# shield.net
KiCad netlist of a schematic drawn in EAGLE
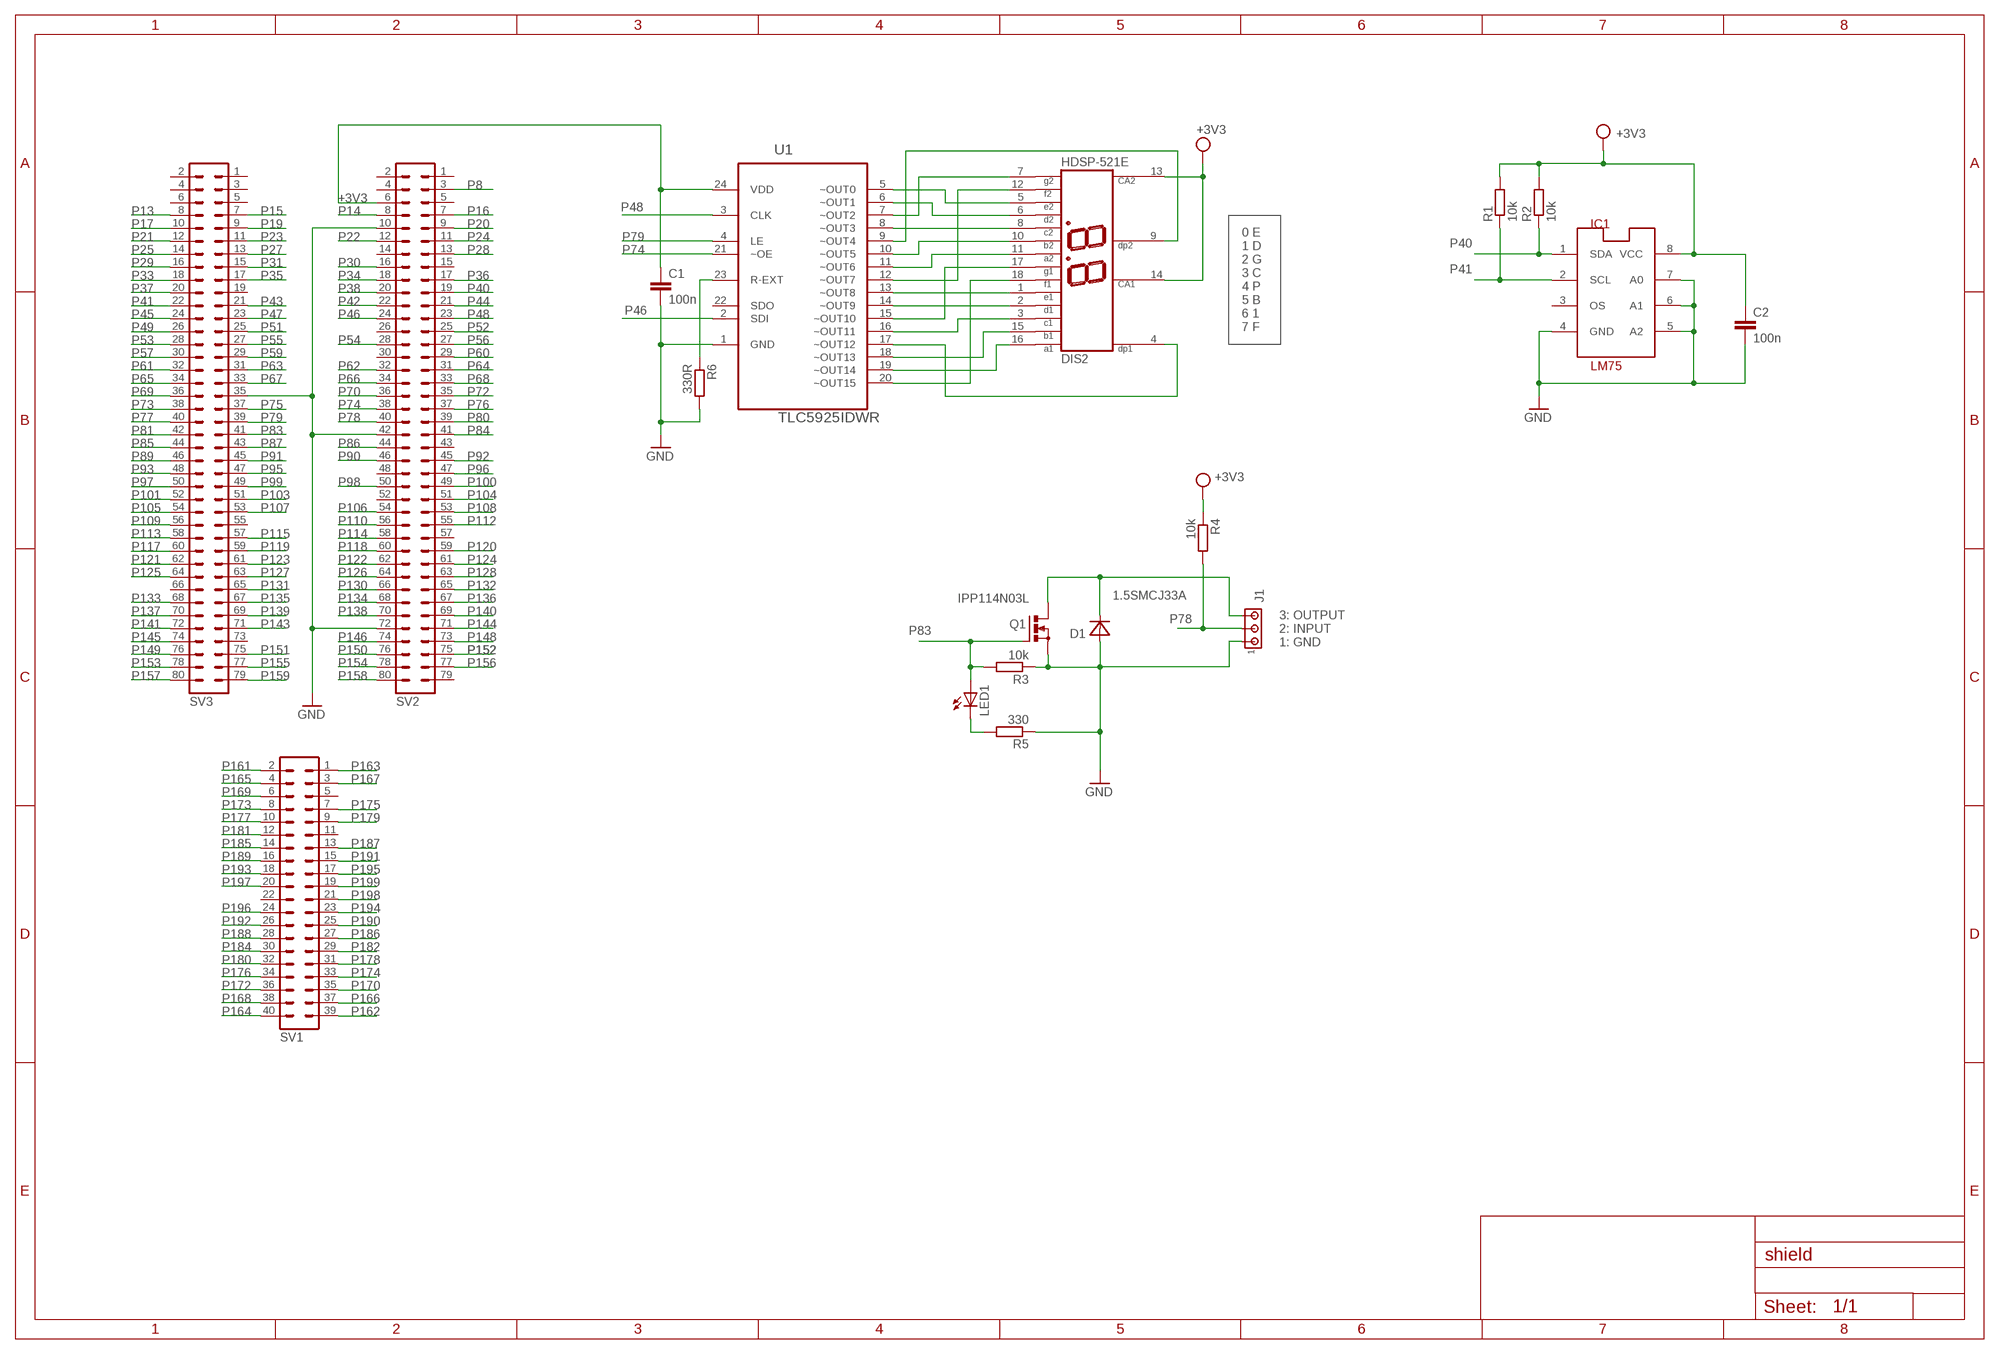
[diagram p0: schematic, sheet 1]

(export (version "E")
  (design (tool "Eeschema 10.0.6"))
  (components
    (comp (ref "C1")
      (value "100n")
      (footprint "eagle-import:C2.5-2")
      (libsource (lib "eagle-import") (part "C2.5/2"))
    )
    (comp (ref "C2")
      (value "100n")
      (footprint "eagle-import:C2.5-2")
      (libsource (lib "eagle-import") (part "C2.5/2"))
    )
    (comp (ref "D1")
      (value "1.5SMCJ33A")
      (footprint "eagle-import:DO214AB")
      (libsource (lib "eagle-import") (part "MBRS340"))
    )
    (comp (ref "DIS2")
      (value "HDSP-521E")
      (footprint "eagle-import:HDSP-R")
      (libsource (lib "eagle-import") (part "HD-K121"))
    )
    (comp (ref "IC1")
      (value "LM75")
      (footprint "eagle-import:SO8_LM75")
      (libsource (lib "eagle-import") (part "LM75_ICN"))
    )
    (comp (ref "J1")
      (value "MTA03-100")
      (footprint "eagle-import:10X03MTA")
      (libsource (lib "eagle-import") (part "MTA03-100"))
    )
    (comp (ref "LED1")
      (value "LED5MM")
      (footprint "eagle-import:LED5MM")
      (libsource (lib "eagle-import") (part "LED5MM"))
    )
    (comp (ref "Q1")
      (value "IPP114N03L")
      (footprint "eagle-import:TO220BV")
      (libsource (lib "eagle-import") (part "BUZ11BV"))
    )
    (comp (ref "R1")
      (value "10k")
      (footprint "eagle-import:0207_10")
      (libsource (lib "eagle-import") (part "R-EU_0207/10"))
    )
    (comp (ref "R2")
      (value "10k")
      (footprint "eagle-import:0207_10")
      (libsource (lib "eagle-import") (part "R-EU_0207/10"))
    )
    (comp (ref "R3")
      (value "10k")
      (footprint "eagle-import:0207_10")
      (libsource (lib "eagle-import") (part "R-EU_0207/10"))
    )
    (comp (ref "R4")
      (value "10k")
      (footprint "eagle-import:0207_10")
      (libsource (lib "eagle-import") (part "R-EU_0207/10"))
    )
    (comp (ref "R5")
      (value "330")
      (footprint "eagle-import:0207_10")
      (libsource (lib "eagle-import") (part "R-EU_0207/10"))
    )
    (comp (ref "R6")
      (value "330R")
      (footprint "eagle-import:0207_10")
      (libsource (lib "eagle-import") (part "R-EU_0207/10"))
    )
    (comp (ref "SV1")
      (value "MA20-2")
      (footprint "eagle-import:MA20-2")
      (libsource (lib "eagle-import") (part "MA20-2"))
    )
    (comp (ref "SV2")
      (value "MA40-2")
      (footprint "eagle-import:MA40-2")
      (libsource (lib "eagle-import") (part "MA40-2"))
    )
    (comp (ref "SV3")
      (value "MA40-2")
      (footprint "eagle-import:MA40-2")
      (libsource (lib "eagle-import") (part "MA40-2"))
    )
    (comp (ref "U1")
      (value "TLC5925IDWR")
      (footprint "eagle-import:SOIC127P1030X265-24N")
      (libsource (lib "eagle-import") (part "TLC5925IDWR"))
    )
  )
  (nets
    (net (code "1") (name "/P8") (class "Default")
      (node (ref "SV2") (pin "3") (pinfunction "3_3") (pintype "passive"))
    )
    (net (code "2") (name "/P13") (class "Default")
      (node (ref "SV3") (pin "8") (pinfunction "8_8") (pintype "passive"))
    )
    (net (code "3") (name "/P14") (class "Default")
      (node (ref "SV2") (pin "8") (pinfunction "8_8") (pintype "passive"))
    )
    (net (code "4") (name "/P15") (class "Default")
      (node (ref "SV3") (pin "7") (pinfunction "7_7") (pintype "passive"))
    )
    (net (code "5") (name "/P16") (class "Default")
      (node (ref "SV2") (pin "7") (pinfunction "7_7") (pintype "passive"))
    )
    (net (code "6") (name "/P17") (class "Default")
      (node (ref "SV3") (pin "10") (pinfunction "10_10") (pintype "passive"))
    )
    (net (code "7") (name "/P19") (class "Default")
      (node (ref "SV3") (pin "9") (pinfunction "9_9") (pintype "passive"))
    )
    (net (code "8") (name "/P20") (class "Default")
      (node (ref "SV2") (pin "9") (pinfunction "9_9") (pintype "passive"))
    )
    (net (code "9") (name "/P21") (class "Default")
      (node (ref "SV3") (pin "12") (pinfunction "12_12") (pintype "passive"))
    )
    (net (code "10") (name "/P22") (class "Default")
      (node (ref "SV2") (pin "12") (pinfunction "12_12") (pintype "passive"))
    )
    (net (code "11") (name "/P23") (class "Default")
      (node (ref "SV3") (pin "11") (pinfunction "11_11") (pintype "passive"))
    )
    (net (code "12") (name "/P24") (class "Default")
      (node (ref "SV2") (pin "11") (pinfunction "11_11") (pintype "passive"))
    )
    (net (code "13") (name "/P25") (class "Default")
      (node (ref "SV3") (pin "14") (pinfunction "14_14") (pintype "passive"))
    )
    (net (code "14") (name "/P27") (class "Default")
      (node (ref "SV3") (pin "13") (pinfunction "13_13") (pintype "passive"))
    )
    (net (code "15") (name "/P28") (class "Default")
      (node (ref "SV2") (pin "13") (pinfunction "13_13") (pintype "passive"))
    )
    (net (code "16") (name "/P29") (class "Default")
      (node (ref "SV3") (pin "16") (pinfunction "16_16") (pintype "passive"))
    )
    (net (code "17") (name "/P30") (class "Default")
      (node (ref "SV2") (pin "16") (pinfunction "16_16") (pintype "passive"))
    )
    (net (code "18") (name "/P31") (class "Default")
      (node (ref "SV3") (pin "15") (pinfunction "15_15") (pintype "passive"))
    )
    (net (code "19") (name "/P33") (class "Default")
      (node (ref "SV3") (pin "18") (pinfunction "18_18") (pintype "passive"))
    )
    (net (code "20") (name "/P34") (class "Default")
      (node (ref "SV2") (pin "18") (pinfunction "18_18") (pintype "passive"))
    )
    (net (code "21") (name "/P35") (class "Default")
      (node (ref "SV3") (pin "17") (pinfunction "17_17") (pintype "passive"))
    )
    (net (code "22") (name "/P36") (class "Default")
      (node (ref "SV2") (pin "17") (pinfunction "17_17") (pintype "passive"))
    )
    (net (code "23") (name "/P37") (class "Default")
      (node (ref "SV3") (pin "20") (pinfunction "20_20") (pintype "passive"))
    )
    (net (code "24") (name "/P38") (class "Default")
      (node (ref "SV2") (pin "20") (pinfunction "20_20") (pintype "passive"))
    )
    (net (code "25") (name "/P40") (class "Default")
      (node (ref "IC1") (pin "1") (pinfunction "SDA_1") (pintype "bidirectional"))
      (node (ref "R2") (pin "1") (pinfunction "1_1") (pintype "passive"))
      (node (ref "SV2") (pin "19") (pinfunction "19_19") (pintype "passive"))
    )
    (net (code "26") (name "/P41") (class "Default")
      (node (ref "IC1") (pin "2") (pinfunction "SCL_2") (pintype "bidirectional"))
      (node (ref "R1") (pin "1") (pinfunction "1_1") (pintype "passive"))
      (node (ref "SV3") (pin "22") (pinfunction "22_22") (pintype "passive"))
    )
    (net (code "27") (name "/P42") (class "Default")
      (node (ref "SV2") (pin "22") (pinfunction "22_22") (pintype "passive"))
    )
    (net (code "28") (name "/P43") (class "Default")
      (node (ref "SV3") (pin "21") (pinfunction "21_21") (pintype "passive"))
    )
    (net (code "29") (name "/P44") (class "Default")
      (node (ref "SV2") (pin "21") (pinfunction "21_21") (pintype "passive"))
    )
    (net (code "30") (name "/P45") (class "Default")
      (node (ref "SV3") (pin "24") (pinfunction "24_24") (pintype "passive"))
    )
    (net (code "31") (name "/P46") (class "Default")
      (node (ref "SV2") (pin "24") (pinfunction "24_24") (pintype "passive"))
      (node (ref "U1") (pin "2") (pinfunction "SDI_2") (pintype "input"))
    )
    (net (code "32") (name "/P47") (class "Default")
      (node (ref "SV3") (pin "23") (pinfunction "23_23") (pintype "passive"))
    )
    (net (code "33") (name "/P48") (class "Default")
      (node (ref "SV2") (pin "23") (pinfunction "23_23") (pintype "passive"))
      (node (ref "U1") (pin "3") (pinfunction "CLK_3") (pintype "input"))
    )
    (net (code "34") (name "/P49") (class "Default")
      (node (ref "SV3") (pin "26") (pinfunction "26_26") (pintype "passive"))
    )
    (net (code "35") (name "/P51") (class "Default")
      (node (ref "SV3") (pin "25") (pinfunction "25_25") (pintype "passive"))
    )
    (net (code "36") (name "/P52") (class "Default")
      (node (ref "SV2") (pin "25") (pinfunction "25_25") (pintype "passive"))
    )
    (net (code "37") (name "/P53") (class "Default")
      (node (ref "SV3") (pin "28") (pinfunction "28_28") (pintype "passive"))
    )
    (net (code "38") (name "/P54") (class "Default")
      (node (ref "SV2") (pin "28") (pinfunction "28_28") (pintype "passive"))
    )
    (net (code "39") (name "/P55") (class "Default")
      (node (ref "SV3") (pin "27") (pinfunction "27_27") (pintype "passive"))
    )
    (net (code "40") (name "/P56") (class "Default")
      (node (ref "SV2") (pin "27") (pinfunction "27_27") (pintype "passive"))
    )
    (net (code "41") (name "/P57") (class "Default")
      (node (ref "SV3") (pin "30") (pinfunction "30_30") (pintype "passive"))
    )
    (net (code "42") (name "/P59") (class "Default")
      (node (ref "SV3") (pin "29") (pinfunction "29_29") (pintype "passive"))
    )
    (net (code "43") (name "/P60") (class "Default")
      (node (ref "SV2") (pin "29") (pinfunction "29_29") (pintype "passive"))
    )
    (net (code "44") (name "/P61") (class "Default")
      (node (ref "SV3") (pin "32") (pinfunction "32_32") (pintype "passive"))
    )
    (net (code "45") (name "/P62") (class "Default")
      (node (ref "SV2") (pin "32") (pinfunction "32_32") (pintype "passive"))
    )
    (net (code "46") (name "/P63") (class "Default")
      (node (ref "SV3") (pin "31") (pinfunction "31_31") (pintype "passive"))
    )
    (net (code "47") (name "/P64") (class "Default")
      (node (ref "SV2") (pin "31") (pinfunction "31_31") (pintype "passive"))
    )
    (net (code "48") (name "/P65") (class "Default")
      (node (ref "SV3") (pin "34") (pinfunction "34_34") (pintype "passive"))
    )
    (net (code "49") (name "/P66") (class "Default")
      (node (ref "SV2") (pin "34") (pinfunction "34_34") (pintype "passive"))
    )
    (net (code "50") (name "/P67") (class "Default")
      (node (ref "SV3") (pin "33") (pinfunction "33_33") (pintype "passive"))
    )
    (net (code "51") (name "/P68") (class "Default")
      (node (ref "SV2") (pin "33") (pinfunction "33_33") (pintype "passive"))
    )
    (net (code "52") (name "/P69") (class "Default")
      (node (ref "SV3") (pin "36") (pinfunction "36_36") (pintype "passive"))
    )
    (net (code "53") (name "/P70") (class "Default")
      (node (ref "SV2") (pin "36") (pinfunction "36_36") (pintype "passive"))
    )
    (net (code "54") (name "/P72") (class "Default")
      (node (ref "SV2") (pin "35") (pinfunction "35_35") (pintype "passive"))
    )
    (net (code "55") (name "/P73") (class "Default")
      (node (ref "SV3") (pin "38") (pinfunction "38_38") (pintype "passive"))
    )
    (net (code "56") (name "/P74") (class "Default")
      (node (ref "SV2") (pin "38") (pinfunction "38_38") (pintype "passive"))
      (node (ref "U1") (pin "21") (pinfunction "~{OE}_21") (pintype "input"))
    )
    (net (code "57") (name "/P75") (class "Default")
      (node (ref "SV3") (pin "37") (pinfunction "37_37") (pintype "passive"))
    )
    (net (code "58") (name "/P76") (class "Default")
      (node (ref "SV2") (pin "37") (pinfunction "37_37") (pintype "passive"))
    )
    (net (code "59") (name "/P77") (class "Default")
      (node (ref "SV3") (pin "40") (pinfunction "40_40") (pintype "passive"))
    )
    (net (code "60") (name "/P78") (class "Default")
      (node (ref "J1") (pin "2") (pinfunction "2_2") (pintype "passive"))
      (node (ref "R4") (pin "2") (pinfunction "2_2") (pintype "passive"))
      (node (ref "SV2") (pin "40") (pinfunction "40_40") (pintype "passive"))
    )
    (net (code "61") (name "/P79") (class "Default")
      (node (ref "SV3") (pin "39") (pinfunction "39_39") (pintype "passive"))
      (node (ref "U1") (pin "4") (pinfunction "LE_4") (pintype "input"))
    )
    (net (code "62") (name "/P80") (class "Default")
      (node (ref "SV2") (pin "39") (pinfunction "39_39") (pintype "passive"))
    )
    (net (code "63") (name "/P81") (class "Default")
      (node (ref "SV3") (pin "42") (pinfunction "42_42") (pintype "passive"))
    )
    (net (code "64") (name "/P83") (class "Default")
      (node (ref "LED1") (pin "A") (pinfunction "A_A") (pintype "passive"))
      (node (ref "Q1") (pin "G") (pinfunction "G_G") (pintype "passive"))
      (node (ref "R3") (pin "2") (pinfunction "2_2") (pintype "passive"))
      (node (ref "SV3") (pin "41") (pinfunction "41_41") (pintype "passive"))
    )
    (net (code "65") (name "/P84") (class "Default")
      (node (ref "SV2") (pin "41") (pinfunction "41_41") (pintype "passive"))
    )
    (net (code "66") (name "/P85") (class "Default")
      (node (ref "SV3") (pin "44") (pinfunction "44_44") (pintype "passive"))
    )
    (net (code "67") (name "/P86") (class "Default")
      (node (ref "SV2") (pin "44") (pinfunction "44_44") (pintype "passive"))
    )
    (net (code "68") (name "/P87") (class "Default")
      (node (ref "SV3") (pin "43") (pinfunction "43_43") (pintype "passive"))
    )
    (net (code "69") (name "/P89") (class "Default")
      (node (ref "SV3") (pin "46") (pinfunction "46_46") (pintype "passive"))
    )
    (net (code "70") (name "/P90") (class "Default")
      (node (ref "SV2") (pin "46") (pinfunction "46_46") (pintype "passive"))
    )
    (net (code "71") (name "/P91") (class "Default")
      (node (ref "SV3") (pin "45") (pinfunction "45_45") (pintype "passive"))
    )
    (net (code "72") (name "/P92") (class "Default")
      (node (ref "SV2") (pin "45") (pinfunction "45_45") (pintype "passive"))
    )
    (net (code "73") (name "/P93") (class "Default")
      (node (ref "SV3") (pin "48") (pinfunction "48_48") (pintype "passive"))
    )
    (net (code "74") (name "/P95") (class "Default")
      (node (ref "SV3") (pin "47") (pinfunction "47_47") (pintype "passive"))
    )
    (net (code "75") (name "/P96") (class "Default")
      (node (ref "SV2") (pin "47") (pinfunction "47_47") (pintype "passive"))
    )
    (net (code "76") (name "/P97") (class "Default")
      (node (ref "SV3") (pin "50") (pinfunction "50_50") (pintype "passive"))
    )
    (net (code "77") (name "/P98") (class "Default")
      (node (ref "SV2") (pin "50") (pinfunction "50_50") (pintype "passive"))
    )
    (net (code "78") (name "/P99") (class "Default")
      (node (ref "SV3") (pin "49") (pinfunction "49_49") (pintype "passive"))
    )
    (net (code "79") (name "/P100") (class "Default")
      (node (ref "SV2") (pin "49") (pinfunction "49_49") (pintype "passive"))
    )
    (net (code "80") (name "/P101") (class "Default")
      (node (ref "SV3") (pin "52") (pinfunction "52_52") (pintype "passive"))
    )
    (net (code "81") (name "/P103") (class "Default")
      (node (ref "SV3") (pin "51") (pinfunction "51_51") (pintype "passive"))
    )
    (net (code "82") (name "/P104") (class "Default")
      (node (ref "SV2") (pin "51") (pinfunction "51_51") (pintype "passive"))
    )
    (net (code "83") (name "/P105") (class "Default")
      (node (ref "SV3") (pin "54") (pinfunction "54_54") (pintype "passive"))
    )
    (net (code "84") (name "/P106") (class "Default")
      (node (ref "SV2") (pin "54") (pinfunction "54_54") (pintype "passive"))
    )
    (net (code "85") (name "/P107") (class "Default")
      (node (ref "SV3") (pin "53") (pinfunction "53_53") (pintype "passive"))
    )
    (net (code "86") (name "/P108") (class "Default")
      (node (ref "SV2") (pin "53") (pinfunction "53_53") (pintype "passive"))
    )
    (net (code "87") (name "/P109") (class "Default")
      (node (ref "SV3") (pin "56") (pinfunction "56_56") (pintype "passive"))
    )
    (net (code "88") (name "/P110") (class "Default")
      (node (ref "SV2") (pin "56") (pinfunction "56_56") (pintype "passive"))
    )
    (net (code "89") (name "/P112") (class "Default")
      (node (ref "SV2") (pin "55") (pinfunction "55_55") (pintype "passive"))
    )
    (net (code "90") (name "/P113") (class "Default")
      (node (ref "SV3") (pin "58") (pinfunction "58_58") (pintype "passive"))
    )
    (net (code "91") (name "/P114") (class "Default")
      (node (ref "SV2") (pin "58") (pinfunction "58_58") (pintype "passive"))
    )
    (net (code "92") (name "/P115") (class "Default")
      (node (ref "SV3") (pin "57") (pinfunction "57_57") (pintype "passive"))
    )
    (net (code "93") (name "/P117") (class "Default")
      (node (ref "SV3") (pin "60") (pinfunction "60_60") (pintype "passive"))
    )
    (net (code "94") (name "/P118") (class "Default")
      (node (ref "SV2") (pin "60") (pinfunction "60_60") (pintype "passive"))
    )
    (net (code "95") (name "/P119") (class "Default")
      (node (ref "SV3") (pin "59") (pinfunction "59_59") (pintype "passive"))
    )
    (net (code "96") (name "/P120") (class "Default")
      (node (ref "SV2") (pin "59") (pinfunction "59_59") (pintype "passive"))
    )
    (net (code "97") (name "/P121") (class "Default")
      (node (ref "SV3") (pin "62") (pinfunction "62_62") (pintype "passive"))
    )
    (net (code "98") (name "/P122") (class "Default")
      (node (ref "SV2") (pin "62") (pinfunction "62_62") (pintype "passive"))
    )
    (net (code "99") (name "/P123") (class "Default")
      (node (ref "SV3") (pin "61") (pinfunction "61_61") (pintype "passive"))
    )
    (net (code "100") (name "/P124") (class "Default")
      (node (ref "SV2") (pin "61") (pinfunction "61_61") (pintype "passive"))
    )
    (net (code "101") (name "/P125") (class "Default")
      (node (ref "SV3") (pin "64") (pinfunction "64_64") (pintype "passive"))
    )
    (net (code "102") (name "/P126") (class "Default")
      (node (ref "SV2") (pin "64") (pinfunction "64_64") (pintype "passive"))
    )
    (net (code "103") (name "/P127") (class "Default")
      (node (ref "SV3") (pin "63") (pinfunction "63_63") (pintype "passive"))
    )
    (net (code "104") (name "/P128") (class "Default")
      (node (ref "SV2") (pin "63") (pinfunction "63_63") (pintype "passive"))
    )
    (net (code "105") (name "/P130") (class "Default")
      (node (ref "SV2") (pin "66") (pinfunction "66_66") (pintype "passive"))
    )
    (net (code "106") (name "/P131") (class "Default")
      (node (ref "SV3") (pin "65") (pinfunction "65_65") (pintype "passive"))
    )
    (net (code "107") (name "/P132") (class "Default")
      (node (ref "SV2") (pin "65") (pinfunction "65_65") (pintype "passive"))
    )
    (net (code "108") (name "/P133") (class "Default")
      (node (ref "SV3") (pin "68") (pinfunction "68_68") (pintype "passive"))
    )
    (net (code "109") (name "/P134") (class "Default")
      (node (ref "SV2") (pin "68") (pinfunction "68_68") (pintype "passive"))
    )
    (net (code "110") (name "/P135") (class "Default")
      (node (ref "SV3") (pin "67") (pinfunction "67_67") (pintype "passive"))
    )
    (net (code "111") (name "/P136") (class "Default")
      (node (ref "SV2") (pin "67") (pinfunction "67_67") (pintype "passive"))
    )
    (net (code "112") (name "/P137") (class "Default")
      (node (ref "SV3") (pin "70") (pinfunction "70_70") (pintype "passive"))
    )
    (net (code "113") (name "/P138") (class "Default")
      (node (ref "SV2") (pin "70") (pinfunction "70_70") (pintype "passive"))
    )
    (net (code "114") (name "/P139") (class "Default")
      (node (ref "SV3") (pin "69") (pinfunction "69_69") (pintype "passive"))
    )
    (net (code "115") (name "/P140") (class "Default")
      (node (ref "SV2") (pin "69") (pinfunction "69_69") (pintype "passive"))
    )
    (net (code "116") (name "/P141") (class "Default")
      (node (ref "SV3") (pin "72") (pinfunction "72_72") (pintype "passive"))
    )
    (net (code "117") (name "/P143") (class "Default")
      (node (ref "SV3") (pin "71") (pinfunction "71_71") (pintype "passive"))
    )
    (net (code "118") (name "/P144") (class "Default")
      (node (ref "SV2") (pin "71") (pinfunction "71_71") (pintype "passive"))
    )
    (net (code "119") (name "/P145") (class "Default")
      (node (ref "SV3") (pin "74") (pinfunction "74_74") (pintype "passive"))
    )
    (net (code "120") (name "/P146") (class "Default")
      (node (ref "SV2") (pin "74") (pinfunction "74_74") (pintype "passive"))
    )
    (net (code "121") (name "/P148") (class "Default")
      (node (ref "SV2") (pin "73") (pinfunction "73_73") (pintype "passive"))
    )
    (net (code "122") (name "/P149") (class "Default")
      (node (ref "SV3") (pin "76") (pinfunction "76_76") (pintype "passive"))
    )
    (net (code "123") (name "/P150") (class "Default")
      (node (ref "SV2") (pin "76") (pinfunction "76_76") (pintype "passive"))
    )
    (net (code "124") (name "/P151") (class "Default")
      (node (ref "SV3") (pin "75") (pinfunction "75_75") (pintype "passive"))
    )
    (net (code "125") (name "/P152") (class "Default")
      (node (ref "SV2") (pin "75") (pinfunction "75_75") (pintype "passive"))
    )
    (net (code "126") (name "/P153") (class "Default")
      (node (ref "SV3") (pin "78") (pinfunction "78_78") (pintype "passive"))
    )
    (net (code "127") (name "/P154") (class "Default")
      (node (ref "SV2") (pin "78") (pinfunction "78_78") (pintype "passive"))
    )
    (net (code "128") (name "/P155") (class "Default")
      (node (ref "SV3") (pin "77") (pinfunction "77_77") (pintype "passive"))
    )
    (net (code "129") (name "/P156") (class "Default")
      (node (ref "SV2") (pin "77") (pinfunction "77_77") (pintype "passive"))
    )
    (net (code "130") (name "/P157") (class "Default")
      (node (ref "SV3") (pin "80") (pinfunction "80_80") (pintype "passive"))
    )
    (net (code "131") (name "/P158") (class "Default")
      (node (ref "SV2") (pin "80") (pinfunction "80_80") (pintype "passive"))
    )
    (net (code "132") (name "/P159") (class "Default")
      (node (ref "SV3") (pin "79") (pinfunction "79_79") (pintype "passive"))
    )
    (net (code "133") (name "/P161") (class "Default")
      (node (ref "SV1") (pin "2") (pinfunction "2_2") (pintype "passive"))
    )
    (net (code "134") (name "/P162") (class "Default")
      (node (ref "SV1") (pin "39") (pinfunction "39_39") (pintype "passive"))
    )
    (net (code "135") (name "/P163") (class "Default")
      (node (ref "SV1") (pin "1") (pinfunction "1_1") (pintype "passive"))
    )
    (net (code "136") (name "/P164") (class "Default")
      (node (ref "SV1") (pin "40") (pinfunction "40_40") (pintype "passive"))
    )
    (net (code "137") (name "/P165") (class "Default")
      (node (ref "SV1") (pin "4") (pinfunction "4_4") (pintype "passive"))
    )
    (net (code "138") (name "/P166") (class "Default")
      (node (ref "SV1") (pin "37") (pinfunction "37_37") (pintype "passive"))
    )
    (net (code "139") (name "/P167") (class "Default")
      (node (ref "SV1") (pin "3") (pinfunction "3_3") (pintype "passive"))
    )
    (net (code "140") (name "/P168") (class "Default")
      (node (ref "SV1") (pin "38") (pinfunction "38_38") (pintype "passive"))
    )
    (net (code "141") (name "/P169") (class "Default")
      (node (ref "SV1") (pin "6") (pinfunction "6_6") (pintype "passive"))
    )
    (net (code "142") (name "/P170") (class "Default")
      (node (ref "SV1") (pin "35") (pinfunction "35_35") (pintype "passive"))
    )
    (net (code "143") (name "/P172") (class "Default")
      (node (ref "SV1") (pin "36") (pinfunction "36_36") (pintype "passive"))
    )
    (net (code "144") (name "/P173") (class "Default")
      (node (ref "SV1") (pin "8") (pinfunction "8_8") (pintype "passive"))
    )
    (net (code "145") (name "/P174") (class "Default")
      (node (ref "SV1") (pin "33") (pinfunction "33_33") (pintype "passive"))
    )
    (net (code "146") (name "/P175") (class "Default")
      (node (ref "SV1") (pin "7") (pinfunction "7_7") (pintype "passive"))
    )
    (net (code "147") (name "/P176") (class "Default")
      (node (ref "SV1") (pin "34") (pinfunction "34_34") (pintype "passive"))
    )
    (net (code "148") (name "/P177") (class "Default")
      (node (ref "SV1") (pin "10") (pinfunction "10_10") (pintype "passive"))
    )
    (net (code "149") (name "/P178") (class "Default")
      (node (ref "SV1") (pin "31") (pinfunction "31_31") (pintype "passive"))
    )
    (net (code "150") (name "/P179") (class "Default")
      (node (ref "SV1") (pin "9") (pinfunction "9_9") (pintype "passive"))
    )
    (net (code "151") (name "/P180") (class "Default")
      (node (ref "SV1") (pin "32") (pinfunction "32_32") (pintype "passive"))
    )
    (net (code "152") (name "/P181") (class "Default")
      (node (ref "SV1") (pin "12") (pinfunction "12_12") (pintype "passive"))
    )
    (net (code "153") (name "/P182") (class "Default")
      (node (ref "SV1") (pin "29") (pinfunction "29_29") (pintype "passive"))
    )
    (net (code "154") (name "/P184") (class "Default")
      (node (ref "SV1") (pin "30") (pinfunction "30_30") (pintype "passive"))
    )
    (net (code "155") (name "/P185") (class "Default")
      (node (ref "SV1") (pin "14") (pinfunction "14_14") (pintype "passive"))
    )
    (net (code "156") (name "/P186") (class "Default")
      (node (ref "SV1") (pin "27") (pinfunction "27_27") (pintype "passive"))
    )
    (net (code "157") (name "/P187") (class "Default")
      (node (ref "SV1") (pin "13") (pinfunction "13_13") (pintype "passive"))
    )
    (net (code "158") (name "/P188") (class "Default")
      (node (ref "SV1") (pin "28") (pinfunction "28_28") (pintype "passive"))
    )
    (net (code "159") (name "/P189") (class "Default")
      (node (ref "SV1") (pin "16") (pinfunction "16_16") (pintype "passive"))
    )
    (net (code "160") (name "/P190") (class "Default")
      (node (ref "SV1") (pin "25") (pinfunction "25_25") (pintype "passive"))
    )
    (net (code "161") (name "/P191") (class "Default")
      (node (ref "SV1") (pin "15") (pinfunction "15_15") (pintype "passive"))
    )
    (net (code "162") (name "/P192") (class "Default")
      (node (ref "SV1") (pin "26") (pinfunction "26_26") (pintype "passive"))
    )
    (net (code "163") (name "/P193") (class "Default")
      (node (ref "SV1") (pin "18") (pinfunction "18_18") (pintype "passive"))
    )
    (net (code "164") (name "/P194") (class "Default")
      (node (ref "SV1") (pin "23") (pinfunction "23_23") (pintype "passive"))
    )
    (net (code "165") (name "/P195") (class "Default")
      (node (ref "SV1") (pin "17") (pinfunction "17_17") (pintype "passive"))
    )
    (net (code "166") (name "/P196") (class "Default")
      (node (ref "SV1") (pin "24") (pinfunction "24_24") (pintype "passive"))
    )
    (net (code "167") (name "/P197") (class "Default")
      (node (ref "SV1") (pin "20") (pinfunction "20_20") (pintype "passive"))
    )
    (net (code "168") (name "/P198") (class "Default")
      (node (ref "SV1") (pin "21") (pinfunction "21_21") (pintype "passive"))
    )
    (net (code "169") (name "/P199") (class "Default")
      (node (ref "SV1") (pin "19") (pinfunction "19_19") (pintype "passive"))
    )
    (net (code "170") (name "GND") (class "Default")
      (node (ref "C1") (pin "2") (pinfunction "2_2") (pintype "passive"))
      (node (ref "C2") (pin "2") (pinfunction "2_2") (pintype "passive"))
      (node (ref "D1") (pin "A") (pinfunction "A_A") (pintype "passive"))
      (node (ref "IC1") (pin "4") (pinfunction "GND_4") (pintype "power_in"))
      (node (ref "IC1") (pin "5") (pinfunction "A2_5") (pintype "input"))
      (node (ref "IC1") (pin "6") (pinfunction "A1_6") (pintype "input"))
      (node (ref "IC1") (pin "7") (pinfunction "A0_7") (pintype "input"))
      (node (ref "J1") (pin "1") (pinfunction "1_1") (pintype "passive"))
      (node (ref "Q1") (pin "S") (pinfunction "S_S") (pintype "passive"))
      (node (ref "R3") (pin "1") (pinfunction "1_1") (pintype "passive"))
      (node (ref "R5") (pin "1") (pinfunction "1_1") (pintype "passive"))
      (node (ref "R6") (pin "2") (pinfunction "2_2") (pintype "passive"))
      (node (ref "SV2") (pin "10") (pinfunction "10_10") (pintype "passive"))
      (node (ref "SV2") (pin "42") (pinfunction "42_42") (pintype "passive"))
      (node (ref "SV2") (pin "72") (pinfunction "72_72") (pintype "passive"))
      (node (ref "SV3") (pin "35") (pinfunction "35_35") (pintype "passive"))
      (node (ref "U1") (pin "1") (pinfunction "GND_1") (pintype "passive"))
    )
    (net (code "171") (name "Net-(D1-C)") (class "Default")
      (node (ref "D1") (pin "K") (pinfunction "C_K") (pintype "passive"))
      (node (ref "J1") (pin "3") (pinfunction "3_3") (pintype "passive"))
      (node (ref "Q1") (pin "D") (pinfunction "D_D") (pintype "passive"))
    )
    (net (code "172") (name "Net-(DIS2-A1)") (class "Default")
      (node (ref "DIS2") (pin "16") (pinfunction "A1_16") (pintype "passive"))
      (node (ref "U1") (pin "19") (pinfunction "~{OUT14}_19") (pintype "output"))
    )
    (net (code "173") (name "Net-(DIS2-A2)") (class "Default")
      (node (ref "DIS2") (pin "11") (pinfunction "A2_11") (pintype "passive"))
      (node (ref "U1") (pin "11") (pinfunction "~{OUT6}_11") (pintype "output"))
    )
    (net (code "174") (name "Net-(DIS2-B1)") (class "Default")
      (node (ref "DIS2") (pin "15") (pinfunction "B1_15") (pintype "passive"))
      (node (ref "U1") (pin "18") (pinfunction "~{OUT13}_18") (pintype "output"))
    )
    (net (code "175") (name "Net-(DIS2-B2)") (class "Default")
      (node (ref "DIS2") (pin "10") (pinfunction "B2_10") (pintype "passive"))
      (node (ref "U1") (pin "10") (pinfunction "~{OUT5}_10") (pintype "output"))
    )
    (net (code "176") (name "Net-(DIS2-C1)") (class "Default")
      (node (ref "DIS2") (pin "3") (pinfunction "C1_3") (pintype "passive"))
      (node (ref "U1") (pin "16") (pinfunction "~{OUT11}_16") (pintype "output"))
    )
    (net (code "177") (name "Net-(DIS2-C2)") (class "Default")
      (node (ref "DIS2") (pin "8") (pinfunction "C2_8") (pintype "passive"))
      (node (ref "U1") (pin "8") (pinfunction "~{OUT3}_8") (pintype "output"))
    )
    (net (code "178") (name "Net-(DIS2-D1)") (class "Default")
      (node (ref "DIS2") (pin "2") (pinfunction "D1_2") (pintype "passive"))
      (node (ref "U1") (pin "14") (pinfunction "~{OUT9}_14") (pintype "output"))
    )
    (net (code "179") (name "Net-(DIS2-D2)") (class "Default")
      (node (ref "DIS2") (pin "6") (pinfunction "D2_6") (pintype "passive"))
      (node (ref "U1") (pin "6") (pinfunction "~{OUT1}_6") (pintype "output"))
    )
    (net (code "180") (name "Net-(DIS2-DP1)") (class "Default")
      (node (ref "DIS2") (pin "4") (pinfunction "DP1_4") (pintype "passive"))
      (node (ref "U1") (pin "17") (pinfunction "~{OUT12}_17") (pintype "output"))
    )
    (net (code "181") (name "Net-(DIS2-DP2)") (class "Default")
      (node (ref "DIS2") (pin "9") (pinfunction "DP2_9") (pintype "passive"))
      (node (ref "U1") (pin "9") (pinfunction "~{OUT4}_9") (pintype "output"))
    )
    (net (code "182") (name "Net-(DIS2-E1)") (class "Default")
      (node (ref "DIS2") (pin "1") (pinfunction "E1_1") (pintype "passive"))
      (node (ref "U1") (pin "13") (pinfunction "~{OUT8}_13") (pintype "output"))
    )
    (net (code "183") (name "Net-(DIS2-E2)") (class "Default")
      (node (ref "DIS2") (pin "5") (pinfunction "E2_5") (pintype "passive"))
      (node (ref "U1") (pin "5") (pinfunction "~{OUT0}_5") (pintype "output"))
    )
    (net (code "184") (name "Net-(DIS2-F1)") (class "Default")
      (node (ref "DIS2") (pin "18") (pinfunction "F1_18") (pintype "passive"))
      (node (ref "U1") (pin "20") (pinfunction "~{OUT15}_20") (pintype "output"))
    )
    (net (code "185") (name "Net-(DIS2-F2)") (class "Default")
      (node (ref "DIS2") (pin "12") (pinfunction "F2_12") (pintype "passive"))
      (node (ref "U1") (pin "12") (pinfunction "~{OUT7}_12") (pintype "output"))
    )
    (net (code "186") (name "Net-(DIS2-G1)") (class "Default")
      (node (ref "DIS2") (pin "17") (pinfunction "G1_17") (pintype "passive"))
      (node (ref "U1") (pin "15") (pinfunction "~{OUT10}_15") (pintype "output"))
    )
    (net (code "187") (name "Net-(DIS2-G2)") (class "Default")
      (node (ref "DIS2") (pin "7") (pinfunction "G2_7") (pintype "passive"))
      (node (ref "U1") (pin "7") (pinfunction "~{OUT2}_7") (pintype "output"))
    )
    (net (code "188") (name "Net-(LED1-C)") (class "Default")
      (node (ref "LED1") (pin "K") (pinfunction "C_K") (pintype "passive"))
      (node (ref "R5") (pin "2") (pinfunction "2_2") (pintype "passive"))
    )
    (net (code "189") (name "Net-(U1-R-EXT)") (class "Default")
      (node (ref "R6") (pin "1") (pinfunction "1_1") (pintype "passive"))
      (node (ref "U1") (pin "23") (pinfunction "R-EXT_23") (pintype "input"))
    )
    (net (code "190") (name "VDD") (class "Default")
      (node (ref "C1") (pin "1") (pinfunction "1_1") (pintype "passive"))
      (node (ref "C2") (pin "1") (pinfunction "1_1") (pintype "passive"))
      (node (ref "DIS2") (pin "13") (pinfunction "CA2_13") (pintype "passive"))
      (node (ref "DIS2") (pin "14") (pinfunction "CA1_14") (pintype "passive"))
      (node (ref "IC1") (pin "8") (pinfunction "VCC_8") (pintype "power_in"))
      (node (ref "R1") (pin "2") (pinfunction "2_2") (pintype "passive"))
      (node (ref "R2") (pin "2") (pinfunction "2_2") (pintype "passive"))
      (node (ref "R4") (pin "1") (pinfunction "1_1") (pintype "passive"))
      (node (ref "SV2") (pin "6") (pinfunction "6_6") (pintype "passive"))
      (node (ref "U1") (pin "24") (pinfunction "VDD_24") (pintype "power_in"))
    )
    (net (code "191") (name "unconnected-(IC1-OS-Pad3)") (class "Default")
      (node (ref "IC1") (pin "3") (pinfunction "OS_3") (pintype "output"))
    )
    (net (code "192") (name "unconnected-(SV1-Pad5)") (class "Default")
      (node (ref "SV1") (pin "5") (pinfunction "5_5") (pintype "passive"))
    )
    (net (code "193") (name "unconnected-(SV1-Pad11)") (class "Default")
      (node (ref "SV1") (pin "11") (pinfunction "11_11") (pintype "passive"))
    )
    (net (code "194") (name "unconnected-(SV1-Pad22)") (class "Default")
      (node (ref "SV1") (pin "22") (pinfunction "22_22") (pintype "passive"))
    )
    (net (code "195") (name "unconnected-(SV2-Pad1)") (class "Default")
      (node (ref "SV2") (pin "1") (pinfunction "1_1") (pintype "passive"))
    )
    (net (code "196") (name "unconnected-(SV2-Pad2)") (class "Default")
      (node (ref "SV2") (pin "2") (pinfunction "2_2") (pintype "passive"))
    )
    (net (code "197") (name "unconnected-(SV2-Pad4)") (class "Default")
      (node (ref "SV2") (pin "4") (pinfunction "4_4") (pintype "passive"))
    )
    (net (code "198") (name "unconnected-(SV2-Pad5)") (class "Default")
      (node (ref "SV2") (pin "5") (pinfunction "5_5") (pintype "passive"))
    )
    (net (code "199") (name "unconnected-(SV2-Pad14)") (class "Default")
      (node (ref "SV2") (pin "14") (pinfunction "14_14") (pintype "passive"))
    )
    (net (code "200") (name "unconnected-(SV2-Pad15)") (class "Default")
      (node (ref "SV2") (pin "15") (pinfunction "15_15") (pintype "passive"))
    )
    (net (code "201") (name "unconnected-(SV2-Pad26)") (class "Default")
      (node (ref "SV2") (pin "26") (pinfunction "26_26") (pintype "passive"))
    )
    (net (code "202") (name "unconnected-(SV2-Pad30)") (class "Default")
      (node (ref "SV2") (pin "30") (pinfunction "30_30") (pintype "passive"))
    )
    (net (code "203") (name "unconnected-(SV2-Pad43)") (class "Default")
      (node (ref "SV2") (pin "43") (pinfunction "43_43") (pintype "passive"))
    )
    (net (code "204") (name "unconnected-(SV2-Pad48)") (class "Default")
      (node (ref "SV2") (pin "48") (pinfunction "48_48") (pintype "passive"))
    )
    (net (code "205") (name "unconnected-(SV2-Pad52)") (class "Default")
      (node (ref "SV2") (pin "52") (pinfunction "52_52") (pintype "passive"))
    )
    (net (code "206") (name "unconnected-(SV2-Pad57)") (class "Default")
      (node (ref "SV2") (pin "57") (pinfunction "57_57") (pintype "passive"))
    )
    (net (code "207") (name "unconnected-(SV2-Pad79)") (class "Default")
      (node (ref "SV2") (pin "79") (pinfunction "79_79") (pintype "passive"))
    )
    (net (code "208") (name "unconnected-(SV3-Pad1)") (class "Default")
      (node (ref "SV3") (pin "1") (pinfunction "1_1") (pintype "passive"))
    )
    (net (code "209") (name "unconnected-(SV3-Pad2)") (class "Default")
      (node (ref "SV3") (pin "2") (pinfunction "2_2") (pintype "passive"))
    )
    (net (code "210") (name "unconnected-(SV3-Pad3)") (class "Default")
      (node (ref "SV3") (pin "3") (pinfunction "3_3") (pintype "passive"))
    )
    (net (code "211") (name "unconnected-(SV3-Pad4)") (class "Default")
      (node (ref "SV3") (pin "4") (pinfunction "4_4") (pintype "passive"))
    )
    (net (code "212") (name "unconnected-(SV3-Pad5)") (class "Default")
      (node (ref "SV3") (pin "5") (pinfunction "5_5") (pintype "passive"))
    )
    (net (code "213") (name "unconnected-(SV3-Pad6)") (class "Default")
      (node (ref "SV3") (pin "6") (pinfunction "6_6") (pintype "passive"))
    )
    (net (code "214") (name "unconnected-(SV3-Pad19)") (class "Default")
      (node (ref "SV3") (pin "19") (pinfunction "19_19") (pintype "passive"))
    )
    (net (code "215") (name "unconnected-(SV3-Pad55)") (class "Default")
      (node (ref "SV3") (pin "55") (pinfunction "55_55") (pintype "passive"))
    )
    (net (code "216") (name "unconnected-(SV3-Pad66)") (class "Default")
      (node (ref "SV3") (pin "66") (pinfunction "66_66") (pintype "passive"))
    )
    (net (code "217") (name "unconnected-(SV3-Pad73)") (class "Default")
      (node (ref "SV3") (pin "73") (pinfunction "73_73") (pintype "passive"))
    )
    (net (code "218") (name "unconnected-(U1-SDO-Pad22)") (class "Default")
      (node (ref "U1") (pin "22") (pinfunction "SDO_22") (pintype "bidirectional"))
    )
  )
)
